# Master.net
KiCad netlist of a schematic drawn in Altium Designer
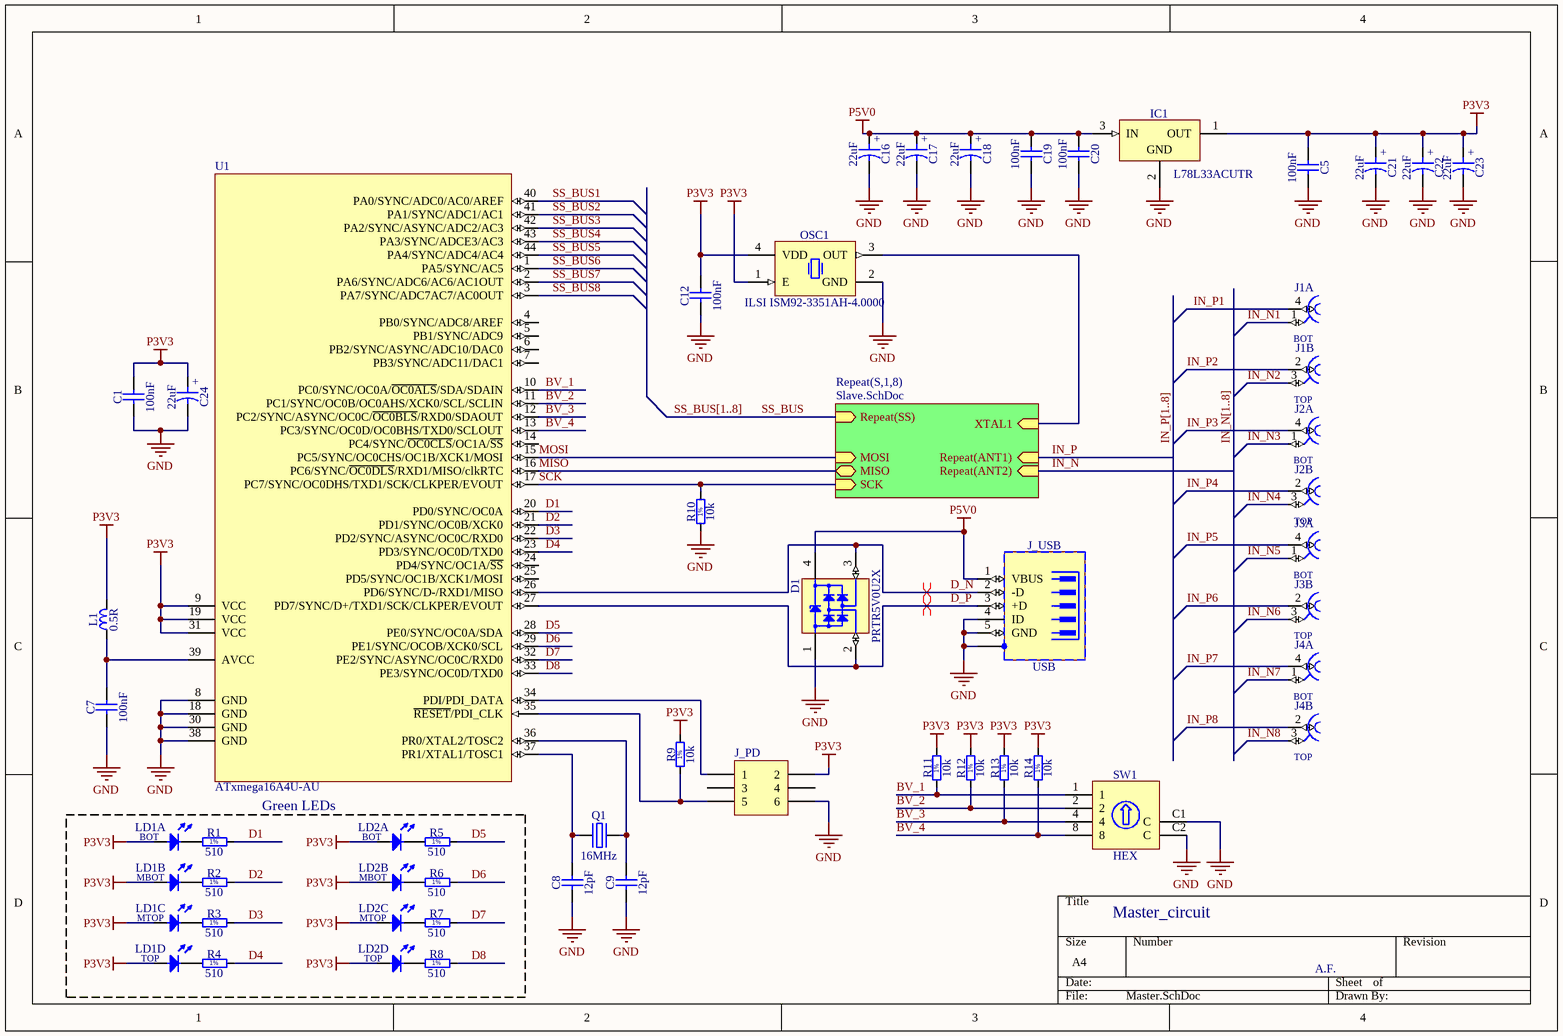
[diagram p0: Master.SchDoc]

(export (version "E")
  (design (tool "Eeschema 10.0.6"))
  (components
    (comp (ref "C1")
      (value "100nF")
      (footprint "CAPC1608X87N")
      (description "Non-polarised capacitor")
      (fields
        (field (name "PART NUMBER") "CC0603_100NF_50V_10%_X5R")
        (field (name "VOLTAGE") "50V")
        (field (name "AUTHOR") "CERN DEM MR")
      )
      (libsource (lib "Capacitors") (part "Capacitor - non polarized"))
    )
    (comp (ref "C5")
      (value "100nF")
      (footprint "CAPC1608X87N")
      (description "Non-polarised capacitor")
      (fields
        (field (name "PART NUMBER") "CC0603_100NF_50V_10%_X5R")
        (field (name "VOLTAGE") "50V")
        (field (name "AUTHOR") "CERN DEM MR")
      )
      (libsource (lib "Capacitors") (part "Capacitor - non polarized"))
    )
    (comp (ref "C7")
      (value "100nF")
      (footprint "CAPC1608X87N")
      (description "Non-polarised capacitor")
      (fields
        (field (name "PART NUMBER") "CC0603_100NF_50V_10%_X5R")
        (field (name "VOLTAGE") "50V")
        (field (name "AUTHOR") "CERN DEM MR")
      )
      (libsource (lib "Capacitors") (part "Capacitor - non polarized"))
    )
    (comp (ref "C8")
      (value "12pF")
      (footprint "CAPC1608X87N")
      (description "Non-polarised capacitor")
      (fields
        (field (name "PART NUMBER") "CC0603_12PF_50V_5%_NP0")
        (field (name "VOLTAGE") "50V")
        (field (name "AUTHOR") "CERN DEM JLC")
      )
      (libsource (lib "Capacitors") (part "Capacitor - non polarized"))
    )
    (comp (ref "C9")
      (value "12pF")
      (footprint "CAPC1608X87N")
      (description "Non-polarised capacitor")
      (fields
        (field (name "PART NUMBER") "CC0603_12PF_50V_5%_NP0")
        (field (name "VOLTAGE") "50V")
        (field (name "AUTHOR") "CERN DEM JLC")
      )
      (libsource (lib "Capacitors") (part "Capacitor - non polarized"))
    )
    (comp (ref "C12")
      (value "100nF")
      (footprint "CAPC1608X87N")
      (description "Non-polarised capacitor")
      (fields
        (field (name "PART NUMBER") "CC0603_100NF_50V_10%_X5R")
        (field (name "VOLTAGE") "50V")
        (field (name "AUTHOR") "CERN DEM MR")
      )
      (libsource (lib "Capacitors") (part "Capacitor - non polarized"))
    )
    (comp (ref "C16")
      (value "22uF")
      (footprint "CAPAE430X540N")
      (description "Polarised capacitor")
      (fields
        (field (name "PART NUMBER") "CAE430-540_22UF_10V_20%")
        (field (name "VOLTAGE") "10V")
        (field (name "AUTHOR") "CERN DEM JLC")
      )
      (libsource (lib "Capacitors") (part "Capacitor - polarized"))
    )
    (comp (ref "C17")
      (value "22uF")
      (footprint "CAPAE430X540N")
      (description "Polarised capacitor")
      (fields
        (field (name "PART NUMBER") "CAE430-540_22UF_10V_20%")
        (field (name "VOLTAGE") "10V")
        (field (name "AUTHOR") "CERN DEM JLC")
      )
      (libsource (lib "Capacitors") (part "Capacitor - polarized"))
    )
    (comp (ref "C18")
      (value "22uF")
      (footprint "CAPAE430X540N")
      (description "Polarised capacitor")
      (fields
        (field (name "PART NUMBER") "CAE430-540_22UF_10V_20%")
        (field (name "VOLTAGE") "10V")
        (field (name "AUTHOR") "CERN DEM JLC")
      )
      (libsource (lib "Capacitors") (part "Capacitor - polarized"))
    )
    (comp (ref "C19")
      (value "100nF")
      (footprint "CAPC1608X87N")
      (description "Non-polarised capacitor")
      (fields
        (field (name "PART NUMBER") "CC0603_100NF_50V_10%_X5R")
        (field (name "VOLTAGE") "50V")
        (field (name "AUTHOR") "CERN DEM MR")
      )
      (libsource (lib "Capacitors") (part "Capacitor - non polarized"))
    )
    (comp (ref "C20")
      (value "100nF")
      (footprint "CAPC1608X87N")
      (description "Non-polarised capacitor")
      (fields
        (field (name "PART NUMBER") "CC0603_100NF_50V_10%_X5R")
        (field (name "VOLTAGE") "50V")
        (field (name "AUTHOR") "CERN DEM MR")
      )
      (libsource (lib "Capacitors") (part "Capacitor - non polarized"))
    )
    (comp (ref "C21")
      (value "22uF")
      (footprint "CAPAE430X540N")
      (description "Polarised capacitor")
      (fields
        (field (name "PART NUMBER") "CAE430-540_22UF_10V_20%")
        (field (name "VOLTAGE") "10V")
        (field (name "AUTHOR") "CERN DEM JLC")
      )
      (libsource (lib "Capacitors") (part "Capacitor - polarized"))
    )
    (comp (ref "C22")
      (value "22uF")
      (footprint "CAPAE430X540N")
      (description "Polarised capacitor")
      (fields
        (field (name "PART NUMBER") "CAE430-540_22UF_10V_20%")
        (field (name "VOLTAGE") "10V")
        (field (name "AUTHOR") "CERN DEM JLC")
      )
      (libsource (lib "Capacitors") (part "Capacitor - polarized"))
    )
    (comp (ref "C23")
      (value "22uF")
      (footprint "CAPAE430X540N")
      (description "Polarised capacitor")
      (fields
        (field (name "PART NUMBER") "CAE430-540_22UF_10V_20%")
        (field (name "VOLTAGE") "10V")
        (field (name "AUTHOR") "CERN DEM JLC")
      )
      (libsource (lib "Capacitors") (part "Capacitor - polarized"))
    )
    (comp (ref "C24")
      (value "22uF")
      (footprint "CAPAE430X540N")
      (description "Polarised capacitor")
      (fields
        (field (name "PART NUMBER") "CAE430-540_22UF_10V_20%")
        (field (name "VOLTAGE") "10V")
        (field (name "AUTHOR") "CERN DEM JLC")
      )
      (libsource (lib "Capacitors") (part "Capacitor - polarized"))
    )
    (comp (ref "D1")
      (value "PRTR5V0U2X")
      (footprint "SOT190P230X110-4N")
      (description "Ultra Low Capacitance Double Rail-to-Rail ESD Protection Diode")
      (fields
        (field (name "VOLTAGE") "5.5V")
        (field (name "MANUFACTURER") "NXP SEMICONDUCTORS")
        (field (name "AUTHOR") "CERN DEM JLC")
      )
      (libsource (lib "ICs And Semiconductors") (part "PRTR5V0U2X"))
    )
    (comp (ref "IC1")
      (value "L78L33ACUTR")
      (footprint "SOT89")
      (description "3-Terminal Regulator 1=OUT 2=GND 3=IN")
      (fields (field (name "MANUFACTURER") "ST MICROELECTRONICS") (field (name "AUTHOR") "CERN DEM JLC"))
      (libsource (lib "ICs And Semiconductors") (part "REG3 1OUT-2GND-3IN"))
    )
    (comp (ref "J1")
      (value "Family")
      (footprint "RENHOTEC_RHT-610-0049")
      (description "Dual Right Angle 50 Ohm BNC Jack, White Valox Case")
      (fields
        (field (name "PART NUMBER") "RENHOTEC_RHT-610-0049")
        (field (name "MANUFACTURER") "RENHOTEC")
        (field (name "AUTHOR") "GK")
      )
      (libsource (lib "LIBRARY_SCH") (part "CON_BNC_DUAL"))
    )
    (comp (ref "J2")
      (value "Family")
      (footprint "RENHOTEC_RHT-610-0049")
      (description "Dual Right Angle 50 Ohm BNC Jack, White Valox Case")
      (fields
        (field (name "PART NUMBER") "RENHOTEC_RHT-610-0049")
        (field (name "MANUFACTURER") "RENHOTEC")
        (field (name "AUTHOR") "GK")
      )
      (libsource (lib "LIBRARY_SCH") (part "CON_BNC_DUAL"))
    )
    (comp (ref "J3")
      (value "Family")
      (footprint "RENHOTEC_RHT-610-0049")
      (description "Dual Right Angle 50 Ohm BNC Jack, White Valox Case")
      (fields
        (field (name "PART NUMBER") "RENHOTEC_RHT-610-0049")
        (field (name "MANUFACTURER") "RENHOTEC")
        (field (name "AUTHOR") "GK")
      )
      (libsource (lib "LIBRARY_SCH") (part "CON_BNC_DUAL"))
    )
    (comp (ref "J4")
      (value "Family")
      (footprint "RENHOTEC_RHT-610-0049")
      (description "Dual Right Angle 50 Ohm BNC Jack, White Valox Case")
      (fields
        (field (name "PART NUMBER") "RENHOTEC_RHT-610-0049")
        (field (name "MANUFACTURER") "RENHOTEC")
        (field (name "AUTHOR") "GK")
      )
      (libsource (lib "LIBRARY_SCH") (part "CON_BNC_DUAL"))
    )
    (comp (ref "J_PD")
      (value "~")
      (footprint "HDR2X3")
      (description "Header, 3-Pin, Dual row")
      (fields (field (name "PUBLISHER") "Altium Limited"))
      (libsource (lib "Miscellaneous Connectors") (part "Header 3X2"))
    )
    (comp (ref "J_USB")
      (value "USB")
      (footprint "WURTH_651005136521")
      (description "5 Pin + 1 Shield USB Receptacle")
      (fields
        (field (name "PART NUMBER") "WURTH_651005136521")
        (field (name "MANUFACTURER") "WURTH ELEKTRONIK")
        (field (name "AUTHOR") "CERN DEM JLC")
      )
      (libsource (lib "Connectors") (part "Connector USB 5 Pin + 1Shield"))
    )
    (comp (ref "L1")
      (value "0.5R")
      (footprint "Miscellaneous Devices:1608[0603]")
      (description "Ferrite Bead")
      (fields
        (field (name "POWER") "0.5A")
        (field (name "MANUFACTURER") "MURATA")
        (field (name "AUTHOR") "CERN DEM BC")
      )
      (libsource (lib "altium-import") (part "root_1_Inductor_"))
    )
    (comp (ref "LD1")
      (value "Green")
      (footprint "LED_BIVAR_H485CGDL")
      (description "LED x4 Green 1C2A-BOT_3C4A_5C6A_7C8A-TOP")
      (fields
        (field (name "PART NUMBER") "LED_BIVAR_H485CGDL")
        (field (name "MANUFACTURER") "BIVAR")
        (field (name "AUTHOR") "CERN DEM JLC")
      )
      (libsource (lib "RFID_system") (part "LED x4 Green 1C2A-BOT_3C4A_5C6A_7C8A-TOP"))
    )
    (comp (ref "LD2")
      (value "Green")
      (footprint "LED_BIVAR_H485CGDL")
      (description "LED x4 Green 1C2A-BOT_3C4A_5C6A_7C8A-TOP")
      (fields
        (field (name "PART NUMBER") "LED_BIVAR_H485CGDL")
        (field (name "MANUFACTURER") "BIVAR")
        (field (name "AUTHOR") "CERN DEM JLC")
      )
      (libsource (lib "RFID_system") (part "LED x4 Green 1C2A-BOT_3C4A_5C6A_7C8A-TOP"))
    )
    (comp (ref "OSC1")
      (value "ILSI ISM92-3351AH-4.0000")
      (footprint "OSCSC250P320X500X130-4N")
      (description "Oscillator 4 pins 3.3V 4MHz")
      (libsource (lib "Crystals & Oscillators") (part "Oscillator 1E 2GND 3OUT 4VDD"))
    )
    (comp (ref "Q1")
      (value "16MHz")
      (footprint "XTAL1160X490X430")
      (description "Quartz Crystal")
      (fields
        (field (name "PART NUMBER") "XTAL_16MHZ_IQD_LFXTAL003237")
        (field (name "MANUFACTURER") "IQD FREQUENCY PRODUCTS")
        (field (name "AUTHOR") "CERN DEM MR")
      )
      (libsource (lib "ICs And Semiconductors") (part "Quartz Crystal"))
    )
    (comp (ref "R1")
      (value "510")
      (footprint "RESC1608X55N")
      (description "Resistor - 1%")
      (fields
        (field (name "PART NUMBER") "R0603_510R_1%_0.1W_100PPM")
        (field (name "POWER") "0.1W")
        (field (name "AUTHOR") "CERN DEM JLC")
      )
      (libsource (lib "Resistors") (part "Resistor - 1%"))
    )
    (comp (ref "R2")
      (value "510")
      (footprint "RESC1608X55N")
      (description "Resistor - 1%")
      (fields
        (field (name "PART NUMBER") "R0603_510R_1%_0.1W_100PPM")
        (field (name "POWER") "0.1W")
        (field (name "AUTHOR") "CERN DEM JLC")
      )
      (libsource (lib "Resistors") (part "Resistor - 1%"))
    )
    (comp (ref "R3")
      (value "510")
      (footprint "RESC1608X55N")
      (description "Resistor - 1%")
      (fields
        (field (name "PART NUMBER") "R0603_510R_1%_0.1W_100PPM")
        (field (name "POWER") "0.1W")
        (field (name "AUTHOR") "CERN DEM JLC")
      )
      (libsource (lib "Resistors") (part "Resistor - 1%"))
    )
    (comp (ref "R4")
      (value "510")
      (footprint "RESC1608X55N")
      (description "Resistor - 1%")
      (fields
        (field (name "PART NUMBER") "R0603_510R_1%_0.1W_100PPM")
        (field (name "POWER") "0.1W")
        (field (name "AUTHOR") "CERN DEM JLC")
      )
      (libsource (lib "Resistors") (part "Resistor - 1%"))
    )
    (comp (ref "R5")
      (value "510")
      (footprint "RESC1608X55N")
      (description "Resistor - 1%")
      (fields
        (field (name "PART NUMBER") "R0603_510R_1%_0.1W_100PPM")
        (field (name "POWER") "0.1W")
        (field (name "AUTHOR") "CERN DEM JLC")
      )
      (libsource (lib "Resistors") (part "Resistor - 1%"))
    )
    (comp (ref "R6")
      (value "510")
      (footprint "RESC1608X55N")
      (description "Resistor - 1%")
      (fields
        (field (name "PART NUMBER") "R0603_510R_1%_0.1W_100PPM")
        (field (name "POWER") "0.1W")
        (field (name "AUTHOR") "CERN DEM JLC")
      )
      (libsource (lib "Resistors") (part "Resistor - 1%"))
    )
    (comp (ref "R7")
      (value "510")
      (footprint "RESC1608X55N")
      (description "Resistor - 1%")
      (fields
        (field (name "PART NUMBER") "R0603_510R_1%_0.1W_100PPM")
        (field (name "POWER") "0.1W")
        (field (name "AUTHOR") "CERN DEM JLC")
      )
      (libsource (lib "Resistors") (part "Resistor - 1%"))
    )
    (comp (ref "R8")
      (value "510")
      (footprint "RESC1608X55N")
      (description "Resistor - 1%")
      (fields
        (field (name "PART NUMBER") "R0603_510R_1%_0.1W_100PPM")
        (field (name "POWER") "0.1W")
        (field (name "AUTHOR") "CERN DEM JLC")
      )
      (libsource (lib "Resistors") (part "Resistor - 1%"))
    )
    (comp (ref "R9")
      (value "10k")
      (footprint "RESC1608X55N")
      (description "Resistor - 1%")
      (fields
        (field (name "PART NUMBER") "R0603_10K_1%_0.1W_100PPM")
        (field (name "POWER") "0.1W")
        (field (name "AUTHOR") "CERN DEM JLC")
      )
      (libsource (lib "Resistors") (part "Resistor - 1%"))
    )
    (comp (ref "R10")
      (value "10k")
      (footprint "RESC1608X55N")
      (description "Resistor - 1%")
      (fields
        (field (name "PART NUMBER") "R0603_10K_1%_0.1W_100PPM")
        (field (name "POWER") "0.1W")
        (field (name "AUTHOR") "CERN DEM JLC")
      )
      (libsource (lib "Resistors") (part "Resistor - 1%"))
    )
    (comp (ref "R11")
      (value "10k")
      (footprint "RESC1608X55N")
      (description "Resistor - 1%")
      (fields
        (field (name "PART NUMBER") "R0603_10K_1%_0.1W_100PPM")
        (field (name "POWER") "0.1W")
        (field (name "AUTHOR") "CERN DEM JLC")
      )
      (libsource (lib "Resistors") (part "Resistor - 1%"))
    )
    (comp (ref "R12")
      (value "10k")
      (footprint "RESC1608X55N")
      (description "Resistor - 1%")
      (fields
        (field (name "PART NUMBER") "R0603_10K_1%_0.1W_100PPM")
        (field (name "POWER") "0.1W")
        (field (name "AUTHOR") "CERN DEM JLC")
      )
      (libsource (lib "Resistors") (part "Resistor - 1%"))
    )
    (comp (ref "R13")
      (value "10k")
      (footprint "RESC1608X55N")
      (description "Resistor - 1%")
      (fields
        (field (name "PART NUMBER") "R0603_10K_1%_0.1W_100PPM")
        (field (name "POWER") "0.1W")
        (field (name "AUTHOR") "CERN DEM JLC")
      )
      (libsource (lib "Resistors") (part "Resistor - 1%"))
    )
    (comp (ref "R14")
      (value "10k")
      (footprint "RESC1608X55N")
      (description "Resistor - 1%")
      (fields
        (field (name "PART NUMBER") "R0603_10K_1%_0.1W_100PPM")
        (field (name "POWER") "0.1W")
        (field (name "AUTHOR") "CERN DEM JLC")
      )
      (libsource (lib "Resistors") (part "Resistor - 1%"))
    )
    (comp (ref "SW1")
      (value "HEX")
      (footprint "SW_OMRON_A6RV-162RF")
      (description "Rotary Code Switch 1 2 4 8 C1 C2")
      (fields
        (field (name "PART NUMBER") "SW_OMRON_A6RV-162RF or ERD716RR")
        (field (name "MANUFACTURER") "OMRON")
        (field (name "AUTHOR") "CERN DEM JLC")
      )
      (libsource (lib "Eletro-mechanical") (part "SW Rotary 1 2 4 8 C1 C2"))
    )
    (comp (ref "U1")
      (value "ATxmega16A4U-AU")
      (footprint "44A_N")
      (fields (field (name "PUBLISHER") "Altium Limited"))
      (libsource (lib "RFID_system_atxmegau") (part "ATxmega16A4-AU"))
    )
  )
  (nets
    (net (code "2") (name "/BV_1") (class "Default")
      (node (ref "R11") (pin "1") (pinfunction "1_1") (pintype "passive"))
      (node (ref "SW1") (pin "1") (pinfunction "1_1") (pintype "passive"))
      (node (ref "U1") (pin "10") (pinfunction "PC0/SYNC/OC0A/~{OC0ALS}/SDA/SDAIN_10") (pintype "bidirectional"))
    )
    (net (code "3") (name "/BV_2") (class "Default")
      (node (ref "R12") (pin "1") (pinfunction "1_1") (pintype "passive"))
      (node (ref "SW1") (pin "2") (pinfunction "2_2") (pintype "passive"))
      (node (ref "U1") (pin "11") (pinfunction "PC1/SYNC/OC0B/OC0AHS/XCK0/SCL/SCLIN_11") (pintype "bidirectional"))
    )
    (net (code "4") (name "/BV_3") (class "Default")
      (node (ref "R13") (pin "1") (pinfunction "1_1") (pintype "passive"))
      (node (ref "SW1") (pin "4") (pinfunction "4_4") (pintype "passive"))
      (node (ref "U1") (pin "12") (pinfunction "PC2/SYNC/ASYNC/OC0C/~{OC0BLS}/RXD0/SDAOUT_12") (pintype "bidirectional"))
    )
    (net (code "5") (name "/BV_4") (class "Default")
      (node (ref "R14") (pin "1") (pinfunction "1_1") (pintype "passive"))
      (node (ref "SW1") (pin "8") (pinfunction "8_8") (pintype "passive"))
      (node (ref "U1") (pin "13") (pinfunction "PC3/SYNC/OC0D/OC0BHS/TXD0/SCLOUT_13") (pintype "bidirectional"))
    )
    (net (code "6") (name "/D1") (class "Default")
      (node (ref "R1") (pin "2") (pinfunction "2_2") (pintype "passive"))
      (node (ref "U1") (pin "20") (pinfunction "PD0/SYNC/OC0A_20") (pintype "bidirectional"))
    )
    (net (code "7") (name "/D2") (class "Default")
      (node (ref "R2") (pin "2") (pinfunction "2_2") (pintype "passive"))
      (node (ref "U1") (pin "21") (pinfunction "PD1/SYNC/OC0B/XCK0_21") (pintype "bidirectional"))
    )
    (net (code "8") (name "/D3") (class "Default")
      (node (ref "R3") (pin "2") (pinfunction "2_2") (pintype "passive"))
      (node (ref "U1") (pin "22") (pinfunction "PD2/SYNC/ASYNC/OC0C/RXD0_22") (pintype "bidirectional"))
    )
    (net (code "9") (name "/D4") (class "Default")
      (node (ref "R4") (pin "2") (pinfunction "2_2") (pintype "passive"))
      (node (ref "U1") (pin "23") (pinfunction "PD3/SYNC/OC0D/TXD0_23") (pintype "bidirectional"))
    )
    (net (code "10") (name "/D5") (class "Default")
      (node (ref "R5") (pin "2") (pinfunction "2_2") (pintype "passive"))
      (node (ref "U1") (pin "28") (pinfunction "PE0/SYNC/OC0A/SDA_28") (pintype "bidirectional"))
    )
    (net (code "11") (name "/D6") (class "Default")
      (node (ref "R6") (pin "2") (pinfunction "2_2") (pintype "passive"))
      (node (ref "U1") (pin "29") (pinfunction "PE1/SYNC/OCOB/XCK0/SCL_29") (pintype "bidirectional"))
    )
    (net (code "12") (name "/D7") (class "Default")
      (node (ref "R7") (pin "2") (pinfunction "2_2") (pintype "passive"))
      (node (ref "U1") (pin "32") (pinfunction "PE2/SYNC/ASYNC/OC0C/RXD0_32") (pintype "bidirectional"))
    )
    (net (code "13") (name "/D8") (class "Default")
      (node (ref "R8") (pin "2") (pinfunction "2_2") (pintype "passive"))
      (node (ref "U1") (pin "33") (pinfunction "PE3/SYNC/OC0D/TXD0_33") (pintype "bidirectional"))
    )
    (net (code "14") (name "/D_N") (class "Default")
      (node (ref "D1") (pin "3") (pinfunction "I/O2_3") (pintype "bidirectional"))
      (node (ref "J_USB") (pin "2") (pinfunction "-D_2") (pintype "bidirectional"))
      (node (ref "U1") (pin "26") (pinfunction "PD6/SYNC/D-/RXD1/MISO_26") (pintype "bidirectional"))
    )
    (net (code "15") (name "/D_P") (class "Default")
      (node (ref "D1") (pin "2") (pinfunction "I/O1_2") (pintype "bidirectional"))
      (node (ref "J_USB") (pin "3") (pinfunction "+D_3") (pintype "bidirectional"))
      (node (ref "U1") (pin "27") (pinfunction "PD7/SYNC/D+/TXD1/SCK/CLKPER/EVOUT_27") (pintype "bidirectional"))
    )
    (net (code "17") (name "/IN_N1") (class "Default")
      (node (ref "J1") (pin "1") (pinfunction "1_1") (pintype "bidirectional"))
    )
    (net (code "18") (name "/IN_N2") (class "Default")
      (node (ref "J1") (pin "3") (pinfunction "3_3") (pintype "bidirectional"))
    )
    (net (code "19") (name "/IN_N3") (class "Default")
      (node (ref "J2") (pin "1") (pinfunction "1_1") (pintype "bidirectional"))
    )
    (net (code "20") (name "/IN_N4") (class "Default")
      (node (ref "J2") (pin "3") (pinfunction "3_3") (pintype "bidirectional"))
    )
    (net (code "21") (name "/IN_N5") (class "Default")
      (node (ref "J3") (pin "1") (pinfunction "1_1") (pintype "bidirectional"))
    )
    (net (code "22") (name "/IN_N6") (class "Default")
      (node (ref "J3") (pin "3") (pinfunction "3_3") (pintype "bidirectional"))
    )
    (net (code "23") (name "/IN_N7") (class "Default")
      (node (ref "J4") (pin "1") (pinfunction "1_1") (pintype "bidirectional"))
    )
    (net (code "24") (name "/IN_N8") (class "Default")
      (node (ref "J4") (pin "3") (pinfunction "3_3") (pintype "bidirectional"))
    )
    (net (code "27") (name "/IN_P1") (class "Default")
      (node (ref "J1") (pin "4") (pinfunction "4_4") (pintype "bidirectional"))
    )
    (net (code "28") (name "/IN_P2") (class "Default")
      (node (ref "J1") (pin "2") (pinfunction "2_2") (pintype "bidirectional"))
    )
    (net (code "29") (name "/IN_P3") (class "Default")
      (node (ref "J2") (pin "4") (pinfunction "4_4") (pintype "bidirectional"))
    )
    (net (code "30") (name "/IN_P4") (class "Default")
      (node (ref "J2") (pin "2") (pinfunction "2_2") (pintype "bidirectional"))
    )
    (net (code "31") (name "/IN_P5") (class "Default")
      (node (ref "J3") (pin "4") (pinfunction "4_4") (pintype "bidirectional"))
    )
    (net (code "32") (name "/IN_P6") (class "Default")
      (node (ref "J3") (pin "2") (pinfunction "2_2") (pintype "bidirectional"))
    )
    (net (code "33") (name "/IN_P7") (class "Default")
      (node (ref "J4") (pin "4") (pinfunction "4_4") (pintype "bidirectional"))
    )
    (net (code "34") (name "/IN_P8") (class "Default")
      (node (ref "J4") (pin "2") (pinfunction "2_2") (pintype "bidirectional"))
    )
    (net (code "36") (name "/MISO") (class "Default")
      (node (ref "U1") (pin "16") (pinfunction "PC6/SYNC/~{OC0DLS}/RXD1/MISO/clkRTC_16") (pintype "bidirectional"))
    )
    (net (code "37") (name "/MOSI") (class "Default")
      (node (ref "U1") (pin "15") (pinfunction "PC5/SYNC/OC0CHS/OC1B/XCK1/MOSI_15") (pintype "bidirectional"))
    )
    (net (code "38") (name "/SCK") (class "Default")
      (node (ref "R10") (pin "2") (pinfunction "2_2") (pintype "passive"))
      (node (ref "U1") (pin "17") (pinfunction "PC7/SYNC/OC0DHS/TXD1/SCK/CLKPER/EVOUT_17") (pintype "bidirectional"))
    )
    (net (code "40") (name "/SS_BUS1") (class "Default")
      (node (ref "U1") (pin "40") (pinfunction "PA0/SYNC/ADC0/AC0/AREF_40") (pintype "bidirectional"))
    )
    (net (code "41") (name "/SS_BUS2") (class "Default")
      (node (ref "U1") (pin "41") (pinfunction "PA1/SYNC/ADC1/AC1_41") (pintype "bidirectional"))
    )
    (net (code "42") (name "/SS_BUS3") (class "Default")
      (node (ref "U1") (pin "42") (pinfunction "PA2/SYNC/ASYNC/ADC2/AC3_42") (pintype "bidirectional"))
    )
    (net (code "43") (name "/SS_BUS4") (class "Default")
      (node (ref "U1") (pin "43") (pinfunction "PA3/SYNC/ADCE3/AC3_43") (pintype "bidirectional"))
    )
    (net (code "44") (name "/SS_BUS5") (class "Default")
      (node (ref "U1") (pin "44") (pinfunction "PA4/SYNC/ADC4/AC4_44") (pintype "bidirectional"))
    )
    (net (code "45") (name "/SS_BUS6") (class "Default")
      (node (ref "U1") (pin "1") (pinfunction "PA5/SYNC/AC5_1") (pintype "bidirectional"))
    )
    (net (code "46") (name "/SS_BUS7") (class "Default")
      (node (ref "U1") (pin "2") (pinfunction "PA6/SYNC/ADC6/AC6/AC1OUT_2") (pintype "bidirectional"))
    )
    (net (code "47") (name "/SS_BUS8") (class "Default")
      (node (ref "U1") (pin "3") (pinfunction "PA7/SYNC/ADC7AC7/AC0OUT_3") (pintype "bidirectional"))
    )
    (net (code "49") (name "/XTAL1") (class "Default")
      (node (ref "OSC1") (pin "3") (pinfunction "OUT_3") (pintype "output"))
    )
    (net (code "50") (name "GND") (class "Default")
      (node (ref "C1") (pin "1") (pinfunction "1_1") (pintype "passive"))
      (node (ref "C12") (pin "1") (pinfunction "1_1") (pintype "passive"))
      (node (ref "C16") (pin "2") (pinfunction "2_2") (pintype "passive"))
      (node (ref "C17") (pin "2") (pinfunction "2_2") (pintype "passive"))
      (node (ref "C18") (pin "2") (pinfunction "2_2") (pintype "passive"))
      (node (ref "C19") (pin "2") (pinfunction "2_2") (pintype "passive"))
      (node (ref "C20") (pin "2") (pinfunction "2_2") (pintype "passive"))
      (node (ref "C21") (pin "2") (pinfunction "2_2") (pintype "passive"))
      (node (ref "C22") (pin "2") (pinfunction "2_2") (pintype "passive"))
      (node (ref "C23") (pin "2") (pinfunction "2_2") (pintype "passive"))
      (node (ref "C24") (pin "2") (pinfunction "2_2") (pintype "passive"))
      (node (ref "C5") (pin "2") (pinfunction "2_2") (pintype "passive"))
      (node (ref "C7") (pin "1") (pinfunction "1_1") (pintype "passive"))
      (node (ref "C8") (pin "1") (pinfunction "1_1") (pintype "passive"))
      (node (ref "C9") (pin "1") (pinfunction "1_1") (pintype "passive"))
      (node (ref "D1") (pin "1") (pinfunction "GND_1") (pintype "power_in"))
      (node (ref "IC1") (pin "2") (pinfunction "GND_2") (pintype "power_in"))
      (node (ref "J_PD") (pin "6") (pinfunction "6_6") (pintype "passive"))
      (node (ref "J_USB") (pin "4") (pinfunction "ID_4") (pintype "passive"))
      (node (ref "J_USB") (pin "5") (pinfunction "GND_5") (pintype "bidirectional"))
      (node (ref "J_USB") (pin "6") (pinfunction "SH_6") (pintype "power_in"))
      (node (ref "OSC1") (pin "2") (pinfunction "GND_2") (pintype "power_in"))
      (node (ref "R10") (pin "1") (pinfunction "1_1") (pintype "passive"))
      (node (ref "SW1") (pin "C1") (pinfunction "C_C1") (pintype "passive"))
      (node (ref "SW1") (pin "C2") (pinfunction "C_C2") (pintype "passive"))
      (node (ref "U1") (pin "18") (pinfunction "GND_18") (pintype "power_in"))
      (node (ref "U1") (pin "30") (pinfunction "GND_30") (pintype "power_in"))
      (node (ref "U1") (pin "38") (pinfunction "GND_38") (pintype "power_in"))
      (node (ref "U1") (pin "8") (pinfunction "GND_8") (pintype "power_in"))
    )
    (net (code "51") (name "Net-(LD1A-C)") (class "Default")
      (node (ref "LD1") (pin "1") (pinfunction "C_1") (pintype "passive"))
      (node (ref "R1") (pin "1") (pinfunction "1_1") (pintype "passive"))
    )
    (net (code "52") (name "Net-(LD1B-C)") (class "Default")
      (node (ref "LD1") (pin "3") (pinfunction "C_3") (pintype "passive"))
      (node (ref "R2") (pin "1") (pinfunction "1_1") (pintype "passive"))
    )
    (net (code "53") (name "Net-(LD1C-C)") (class "Default")
      (node (ref "LD1") (pin "5") (pinfunction "C_5") (pintype "passive"))
      (node (ref "R3") (pin "1") (pinfunction "1_1") (pintype "passive"))
    )
    (net (code "54") (name "Net-(LD1D-C)") (class "Default")
      (node (ref "LD1") (pin "7") (pinfunction "C_7") (pintype "passive"))
      (node (ref "R4") (pin "1") (pinfunction "1_1") (pintype "passive"))
    )
    (net (code "55") (name "Net-(LD2A-C)") (class "Default")
      (node (ref "LD2") (pin "1") (pinfunction "C_1") (pintype "passive"))
      (node (ref "R5") (pin "1") (pinfunction "1_1") (pintype "passive"))
    )
    (net (code "56") (name "Net-(LD2B-C)") (class "Default")
      (node (ref "LD2") (pin "3") (pinfunction "C_3") (pintype "passive"))
      (node (ref "R6") (pin "1") (pinfunction "1_1") (pintype "passive"))
    )
    (net (code "57") (name "Net-(LD2C-C)") (class "Default")
      (node (ref "LD2") (pin "5") (pinfunction "C_5") (pintype "passive"))
      (node (ref "R7") (pin "1") (pinfunction "1_1") (pintype "passive"))
    )
    (net (code "58") (name "Net-(LD2D-C)") (class "Default")
      (node (ref "LD2") (pin "7") (pinfunction "C_7") (pintype "passive"))
      (node (ref "R8") (pin "1") (pinfunction "1_1") (pintype "passive"))
    )
    (net (code "59") (name "Net-(Q1-OSC1)") (class "Default")
      (node (ref "C8") (pin "2") (pinfunction "2_2") (pintype "passive"))
      (node (ref "Q1") (pin "1") (pinfunction "OSC1_1") (pintype "passive"))
      (node (ref "U1") (pin "37") (pinfunction "PR1/XTAL1/TOSC1_37") (pintype "bidirectional"))
    )
    (net (code "60") (name "Net-(Q1-OSC2)") (class "Default")
      (node (ref "C9") (pin "2") (pinfunction "2_2") (pintype "passive"))
      (node (ref "Q1") (pin "2") (pinfunction "OSC2_2") (pintype "passive"))
      (node (ref "U1") (pin "36") (pinfunction "PR0/XTAL2/TOSC2_36") (pintype "bidirectional"))
    )
    (net (code "61") (name "Net-(U1-AVCC)") (class "Default")
      (node (ref "C7") (pin "2") (pinfunction "2_2") (pintype "passive"))
      (node (ref "L1") (pin "1") (pinfunction "1_1") (pintype "passive"))
      (node (ref "U1") (pin "39") (pinfunction "AVCC_39") (pintype "power_in"))
    )
    (net (code "62") (name "Net-(U1-PDI{slash}PDI_DATA)") (class "Default")
      (node (ref "J_PD") (pin "1") (pinfunction "1_1") (pintype "passive"))
      (node (ref "U1") (pin "34") (pinfunction "PDI/PDI_DATA_34") (pintype "bidirectional"))
    )
    (net (code "63") (name "Net-(U1-~{RESET}{slash}PDI_CLK)") (class "Default")
      (node (ref "J_PD") (pin "5") (pinfunction "5_5") (pintype "passive"))
      (node (ref "R9") (pin "1") (pinfunction "1_1") (pintype "passive"))
      (node (ref "U1") (pin "35") (pinfunction "~{RESET}/PDI_CLK_35") (pintype "input"))
    )
    (net (code "64") (name "P3V3") (class "Default")
      (node (ref "C1") (pin "2") (pinfunction "2_2") (pintype "passive"))
      (node (ref "C12") (pin "2") (pinfunction "2_2") (pintype "passive"))
      (node (ref "C21") (pin "1") (pinfunction "1_1") (pintype "passive"))
      (node (ref "C22") (pin "1") (pinfunction "1_1") (pintype "passive"))
      (node (ref "C23") (pin "1") (pinfunction "1_1") (pintype "passive"))
      (node (ref "C24") (pin "1") (pinfunction "1_1") (pintype "passive"))
      (node (ref "C5") (pin "1") (pinfunction "1_1") (pintype "passive"))
      (node (ref "IC1") (pin "1") (pinfunction "OUT_1") (pintype "power_in"))
      (node (ref "J_PD") (pin "2") (pinfunction "2_2") (pintype "passive"))
      (node (ref "L1") (pin "2") (pinfunction "2_2") (pintype "passive"))
      (node (ref "LD1") (pin "2") (pinfunction "A_2") (pintype "passive"))
      (node (ref "LD1") (pin "4") (pinfunction "A_4") (pintype "passive"))
      (node (ref "LD1") (pin "6") (pinfunction "A_6") (pintype "passive"))
      (node (ref "LD1") (pin "8") (pinfunction "A_8") (pintype "passive"))
      (node (ref "LD2") (pin "2") (pinfunction "A_2") (pintype "passive"))
      (node (ref "LD2") (pin "4") (pinfunction "A_4") (pintype "passive"))
      (node (ref "LD2") (pin "6") (pinfunction "A_6") (pintype "passive"))
      (node (ref "LD2") (pin "8") (pinfunction "A_8") (pintype "passive"))
      (node (ref "OSC1") (pin "1") (pinfunction "E_1") (pintype "input"))
      (node (ref "OSC1") (pin "4") (pinfunction "VDD_4") (pintype "power_in"))
      (node (ref "R11") (pin "2") (pinfunction "2_2") (pintype "passive"))
      (node (ref "R12") (pin "2") (pinfunction "2_2") (pintype "passive"))
      (node (ref "R13") (pin "2") (pinfunction "2_2") (pintype "passive"))
      (node (ref "R14") (pin "2") (pinfunction "2_2") (pintype "passive"))
      (node (ref "R9") (pin "2") (pinfunction "2_2") (pintype "passive"))
      (node (ref "U1") (pin "19") (pinfunction "VCC_19") (pintype "power_in"))
      (node (ref "U1") (pin "31") (pinfunction "VCC_31") (pintype "power_in"))
      (node (ref "U1") (pin "9") (pinfunction "VCC_9") (pintype "power_in"))
    )
    (net (code "65") (name "P5V0") (class "Default")
      (node (ref "C16") (pin "1") (pinfunction "1_1") (pintype "passive"))
      (node (ref "C17") (pin "1") (pinfunction "1_1") (pintype "passive"))
      (node (ref "C18") (pin "1") (pinfunction "1_1") (pintype "passive"))
      (node (ref "C19") (pin "1") (pinfunction "1_1") (pintype "passive"))
      (node (ref "C20") (pin "1") (pinfunction "1_1") (pintype "passive"))
      (node (ref "D1") (pin "4") (pinfunction "VCC_4") (pintype "power_in"))
      (node (ref "IC1") (pin "3") (pinfunction "IN_3") (pintype "input"))
      (node (ref "J_USB") (pin "1") (pinfunction "VBUS_1") (pintype "bidirectional"))
    )
    (net (code "66") (name "unconnected-(J_PD-Pad3)") (class "Default")
      (node (ref "J_PD") (pin "3") (pinfunction "3_3") (pintype "passive"))
    )
    (net (code "67") (name "unconnected-(J_PD-Pad4)") (class "Default")
      (node (ref "J_PD") (pin "4") (pinfunction "4_4") (pintype "passive"))
    )
    (net (code "68") (name "unconnected-(U1-PB0{slash}SYNC{slash}ADC8{slash}AREF-Pad4)") (class "Default")
      (node (ref "U1") (pin "4") (pinfunction "PB0/SYNC/ADC8/AREF_4") (pintype "bidirectional"))
    )
    (net (code "69") (name "unconnected-(U1-PB1{slash}SYNC{slash}ADC9-Pad5)") (class "Default")
      (node (ref "U1") (pin "5") (pinfunction "PB1/SYNC/ADC9_5") (pintype "bidirectional"))
    )
    (net (code "70") (name "unconnected-(U1-PB2{slash}SYNC{slash}ASYNC{slash}ADC10{slash}DAC0-Pad6)") (class "Default")
      (node (ref "U1") (pin "6") (pinfunction "PB2/SYNC/ASYNC/ADC10/DAC0_6") (pintype "bidirectional"))
    )
    (net (code "71") (name "unconnected-(U1-PB3{slash}SYNC{slash}ADC11{slash}DAC1-Pad7)") (class "Default")
      (node (ref "U1") (pin "7") (pinfunction "PB3/SYNC/ADC11/DAC1_7") (pintype "bidirectional"))
    )
    (net (code "72") (name "unconnected-(U1-PC4{slash}SYNC{slash}~{OC0CLS}{slash}OC1A{slash}~{SS}-Pad14)") (class "Default")
      (node (ref "U1") (pin "14") (pinfunction "PC4/SYNC/~{OC0CLS}/OC1A/~{SS}_14") (pintype "bidirectional"))
    )
    (net (code "73") (name "unconnected-(U1-PD4{slash}SYNC{slash}OC1A{slash}~{SS}-Pad24)") (class "Default")
      (node (ref "U1") (pin "24") (pinfunction "PD4/SYNC/OC1A/~{SS}_24") (pintype "bidirectional"))
    )
    (net (code "74") (name "unconnected-(U1-PD5{slash}SYNC{slash}OC1B{slash}XCK1{slash}MOSI-Pad25)") (class "Default")
      (node (ref "U1") (pin "25") (pinfunction "PD5/SYNC/OC1B/XCK1/MOSI_25") (pintype "bidirectional"))
    )
  )
)
